# peripherals_1_0.net
KiCad netlist of a schematic drawn in EAGLE
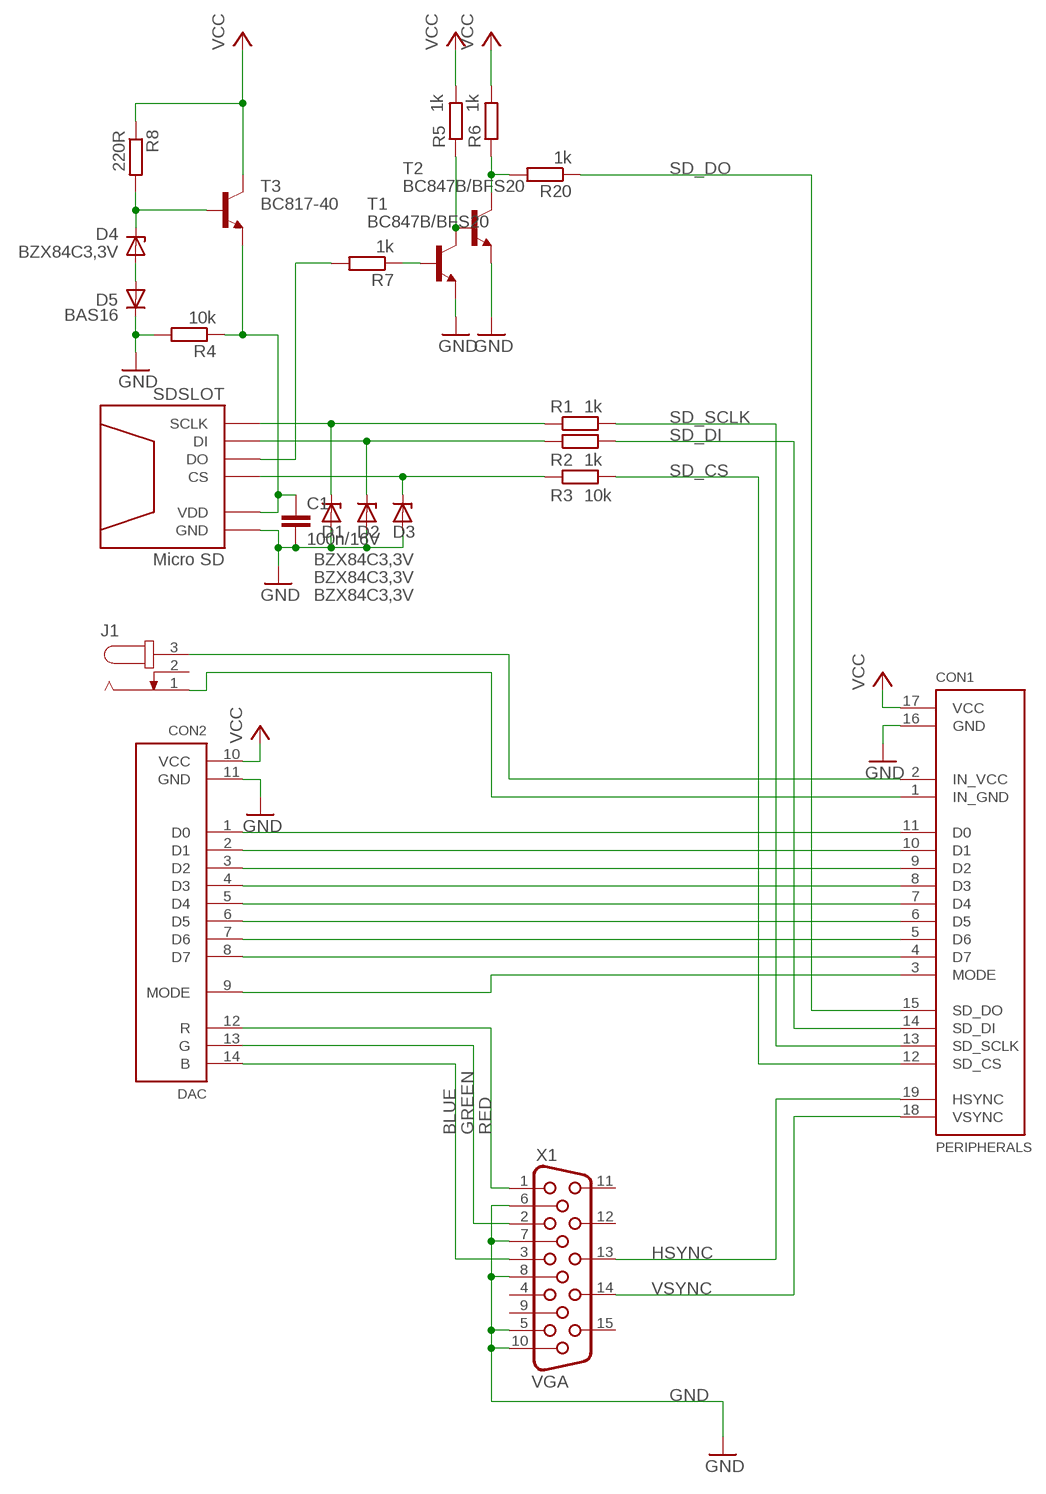
[diagram p0: schematic, sheet 1]

(export (version "E")
  (design (tool "Eeschema 10.0.6"))
  (components
    (comp (ref "C1")
      (value "100n/16V")
      (footprint "eagle-import:C0603")
      (libsource (lib "eagle-import") (part "C-EUC0603"))
    )
    (comp (ref "CON1")
      (value "PERIPHERALS")
      (footprint "eagle-import:PERIPHERALS_CON")
      (libsource (lib "eagle-import") (part "PERIPHERALS"))
    )
    (comp (ref "CON2")
      (value "DAC")
      (footprint "eagle-import:DAC_CON")
      (libsource (lib "eagle-import") (part "DAC"))
    )
    (comp (ref "D1")
      (value "BZX84C3,3V")
      (footprint "eagle-import:SOT23")
      (libsource (lib "eagle-import") (part "ZENER-DIODESOT23"))
    )
    (comp (ref "D2")
      (value "BZX84C3,3V")
      (footprint "eagle-import:SOT23")
      (libsource (lib "eagle-import") (part "ZENER-DIODESOT23"))
    )
    (comp (ref "D3")
      (value "BZX84C3,3V")
      (footprint "eagle-import:SOT23")
      (libsource (lib "eagle-import") (part "ZENER-DIODESOT23"))
    )
    (comp (ref "D4")
      (value "BZX84C3,3V")
      (footprint "eagle-import:SOT23")
      (libsource (lib "eagle-import") (part "ZENER-DIODESOT23"))
    )
    (comp (ref "D5")
      (value "BAS16")
      (footprint "eagle-import:SOT23")
      (libsource (lib "eagle-import") (part "D-A1-C3"))
    )
    (comp (ref "J1")
      (value "JACK-PLUG1")
      (footprint "eagle-import:SPC4078")
      (libsource (lib "eagle-import") (part "JACK-PLUG1"))
    )
    (comp (ref "R1")
      (value "1k")
      (footprint "eagle-import:0204_7")
      (libsource (lib "eagle-import") (part "R-EU_0204/7"))
    )
    (comp (ref "R2")
      (value "1k")
      (footprint "eagle-import:0204_7")
      (libsource (lib "eagle-import") (part "R-EU_0204/7"))
    )
    (comp (ref "R3")
      (value "10k")
      (footprint "eagle-import:0204_7")
      (libsource (lib "eagle-import") (part "R-EU_0204/7"))
    )
    (comp (ref "R4")
      (value "10k")
      (footprint "eagle-import:0204_7")
      (libsource (lib "eagle-import") (part "R-EU_0204/7"))
    )
    (comp (ref "R5")
      (value "1k")
      (footprint "eagle-import:0204_7")
      (libsource (lib "eagle-import") (part "R-EU_0204/7"))
    )
    (comp (ref "R6")
      (value "1k")
      (footprint "eagle-import:0204_7")
      (libsource (lib "eagle-import") (part "R-EU_0204/7"))
    )
    (comp (ref "R7")
      (value "1k")
      (footprint "eagle-import:0204_7")
      (libsource (lib "eagle-import") (part "R-EU_0204/7"))
    )
    (comp (ref "R8")
      (value "220R")
      (footprint "eagle-import:R0603")
      (libsource (lib "eagle-import") (part "R-EU_R0603"))
    )
    (comp (ref "R20")
      (value "1k")
      (footprint "eagle-import:0204_7")
      (libsource (lib "eagle-import") (part "R-EU_0204/7"))
    )
    (comp (ref "SDSLOT")
      (value "Micro SD")
      (footprint "eagle-import:MICRO_SD_ATTEND")
      (libsource (lib "eagle-import") (part "SD_SPI"))
    )
    (comp (ref "T1")
      (value "BC847B/BFS20")
      (footprint "eagle-import:SOT23-BEC")
      (libsource (lib "eagle-import") (part "-NPN-SOT23-BECBC817-40"))
    )
    (comp (ref "T2")
      (value "BC847B/BFS20")
      (footprint "eagle-import:SOT23-BEC")
      (libsource (lib "eagle-import") (part "-NPN-SOT23-BECBC817-40"))
    )
    (comp (ref "T3")
      (value "BC817-40")
      (footprint "eagle-import:SOT23-BEC")
      (libsource (lib "eagle-import") (part "-NPN-SOT23-BECBC817-40"))
    )
    (comp (ref "X1")
      (value "VGA")
      (footprint "eagle-import:HDF15H")
      (libsource (lib "eagle-import") (part "HF15H"))
    )
  )
  (nets
    (net (code "1") (name "/BLUE") (class "Default")
      (node (ref "CON2") (pin "14") (pinfunction "B_14") (pintype "output"))
      (node (ref "X1") (pin "3") (pinfunction "3_3") (pintype "passive"))
    )
    (net (code "2") (name "/GREEN") (class "Default")
      (node (ref "CON2") (pin "13") (pinfunction "G_13") (pintype "output"))
      (node (ref "X1") (pin "2") (pinfunction "2_2") (pintype "passive"))
    )
    (net (code "3") (name "/HSYNC") (class "Default")
      (node (ref "CON1") (pin "19") (pinfunction "HSYNC_19") (pintype "bidirectional"))
      (node (ref "X1") (pin "13") (pinfunction "13_13") (pintype "passive"))
    )
    (net (code "4") (name "/RED") (class "Default")
      (node (ref "CON2") (pin "12") (pinfunction "R_12") (pintype "output"))
      (node (ref "X1") (pin "1") (pinfunction "1_1") (pintype "passive"))
    )
    (net (code "5") (name "/SD_CS") (class "Default")
      (node (ref "CON1") (pin "12") (pinfunction "SD_CS_12") (pintype "bidirectional"))
      (node (ref "R3") (pin "2") (pinfunction "2_2") (pintype "passive"))
    )
    (net (code "6") (name "/SD_DI") (class "Default")
      (node (ref "CON1") (pin "14") (pinfunction "SD_DI_14") (pintype "bidirectional"))
      (node (ref "R2") (pin "2") (pinfunction "2_2") (pintype "passive"))
    )
    (net (code "7") (name "/SD_DO") (class "Default")
      (node (ref "CON1") (pin "15") (pinfunction "SD_DO_15") (pintype "bidirectional"))
      (node (ref "R20") (pin "1") (pinfunction "1_1") (pintype "passive"))
    )
    (net (code "8") (name "/SD_SCLK") (class "Default")
      (node (ref "CON1") (pin "13") (pinfunction "SD_SCLK_13") (pintype "bidirectional"))
      (node (ref "R1") (pin "2") (pinfunction "2_2") (pintype "passive"))
    )
    (net (code "9") (name "/VSYNC") (class "Default")
      (node (ref "CON1") (pin "18") (pinfunction "VSYNC_18") (pintype "bidirectional"))
      (node (ref "X1") (pin "14") (pinfunction "14_14") (pintype "passive"))
    )
    (net (code "10") (name "GND") (class "Default")
      (node (ref "C1") (pin "2") (pinfunction "2_2") (pintype "passive"))
      (node (ref "CON1") (pin "16") (pinfunction "GND_16") (pintype "power_in"))
      (node (ref "CON2") (pin "11") (pinfunction "GND_11") (pintype "power_in"))
      (node (ref "D1") (pin "1") (pinfunction "A_1") (pintype "passive"))
      (node (ref "D2") (pin "1") (pinfunction "A_1") (pintype "passive"))
      (node (ref "D3") (pin "1") (pinfunction "A_1") (pintype "passive"))
      (node (ref "D5") (pin "3") (pinfunction "C_3") (pintype "passive"))
      (node (ref "R4") (pin "2") (pinfunction "2_2") (pintype "passive"))
      (node (ref "SDSLOT") (pin "6") (pinfunction "GND_6") (pintype "power_in"))
      (node (ref "SDSLOT") (pin "CASE1") (pinfunction "GND_CASE1") (pintype "power_in"))
      (node (ref "SDSLOT") (pin "CASE2") (pinfunction "GND_CASE2") (pintype "power_in"))
      (node (ref "SDSLOT") (pin "CASE3") (pinfunction "GND_CASE3") (pintype "power_in"))
      (node (ref "SDSLOT") (pin "CASE4") (pinfunction "GND_CASE4") (pintype "power_in"))
      (node (ref "T1") (pin "E") (pinfunction "E_E") (pintype "passive"))
      (node (ref "T2") (pin "E") (pinfunction "E_E") (pintype "passive"))
      (node (ref "X1") (pin "10") (pinfunction "10_10") (pintype "passive"))
      (node (ref "X1") (pin "5") (pinfunction "5_5") (pintype "passive"))
      (node (ref "X1") (pin "6") (pinfunction "6_6") (pintype "passive"))
      (node (ref "X1") (pin "7") (pinfunction "7_7") (pintype "passive"))
      (node (ref "X1") (pin "8") (pinfunction "8_8") (pintype "passive"))
    )
    (net (code "11") (name "Net-(CON1-D0)") (class "Default")
      (node (ref "CON1") (pin "11") (pinfunction "D0_11") (pintype "bidirectional"))
      (node (ref "CON2") (pin "1") (pinfunction "D0_1") (pintype "input"))
    )
    (net (code "12") (name "Net-(CON1-D1)") (class "Default")
      (node (ref "CON1") (pin "10") (pinfunction "D1_10") (pintype "bidirectional"))
      (node (ref "CON2") (pin "2") (pinfunction "D1_2") (pintype "input"))
    )
    (net (code "13") (name "Net-(CON1-D2)") (class "Default")
      (node (ref "CON1") (pin "9") (pinfunction "D2_9") (pintype "bidirectional"))
      (node (ref "CON2") (pin "3") (pinfunction "D2_3") (pintype "input"))
    )
    (net (code "14") (name "Net-(CON1-D3)") (class "Default")
      (node (ref "CON1") (pin "8") (pinfunction "D3_8") (pintype "bidirectional"))
      (node (ref "CON2") (pin "4") (pinfunction "D3_4") (pintype "input"))
    )
    (net (code "15") (name "Net-(CON1-D4)") (class "Default")
      (node (ref "CON1") (pin "7") (pinfunction "D4_7") (pintype "bidirectional"))
      (node (ref "CON2") (pin "5") (pinfunction "D4_5") (pintype "input"))
    )
    (net (code "16") (name "Net-(CON1-D5)") (class "Default")
      (node (ref "CON1") (pin "6") (pinfunction "D5_6") (pintype "bidirectional"))
      (node (ref "CON2") (pin "6") (pinfunction "D5_6") (pintype "input"))
    )
    (net (code "17") (name "Net-(CON1-D6)") (class "Default")
      (node (ref "CON1") (pin "5") (pinfunction "D6_5") (pintype "bidirectional"))
      (node (ref "CON2") (pin "7") (pinfunction "D6_7") (pintype "input"))
    )
    (net (code "18") (name "Net-(CON1-D7)") (class "Default")
      (node (ref "CON1") (pin "4") (pinfunction "D7_4") (pintype "bidirectional"))
      (node (ref "CON2") (pin "8") (pinfunction "D7_8") (pintype "input"))
    )
    (net (code "19") (name "Net-(CON1-IN_GND)") (class "Default")
      (node (ref "CON1") (pin "1") (pinfunction "IN_GND_1") (pintype "power_in"))
      (node (ref "J1") (pin "1") (pinfunction "1_1") (pintype "passive"))
    )
    (net (code "20") (name "Net-(CON1-IN_VCC)") (class "Default")
      (node (ref "CON1") (pin "2") (pinfunction "IN_VCC_2") (pintype "power_in"))
      (node (ref "J1") (pin "3") (pinfunction "3_3") (pintype "passive"))
    )
    (net (code "21") (name "Net-(CON1-MODE)") (class "Default")
      (node (ref "CON1") (pin "3") (pinfunction "MODE_3") (pintype "bidirectional"))
      (node (ref "CON2") (pin "9") (pinfunction "MODE_9") (pintype "input"))
    )
    (net (code "22") (name "Net-(D1-C)") (class "Default")
      (node (ref "D1") (pin "3") (pinfunction "C_3") (pintype "passive"))
      (node (ref "R1") (pin "1") (pinfunction "1_1") (pintype "passive"))
      (node (ref "SDSLOT") (pin "5") (pinfunction "SCLK_5") (pintype "input"))
    )
    (net (code "23") (name "Net-(D2-C)") (class "Default")
      (node (ref "D2") (pin "3") (pinfunction "C_3") (pintype "passive"))
      (node (ref "R2") (pin "1") (pinfunction "1_1") (pintype "passive"))
      (node (ref "SDSLOT") (pin "3") (pinfunction "DI_3") (pintype "input"))
    )
    (net (code "24") (name "Net-(D3-C)") (class "Default")
      (node (ref "D3") (pin "3") (pinfunction "C_3") (pintype "passive"))
      (node (ref "R3") (pin "1") (pinfunction "1_1") (pintype "passive"))
      (node (ref "SDSLOT") (pin "2") (pinfunction "CS_2") (pintype "input"))
    )
    (net (code "25") (name "Net-(D4-A)") (class "Default")
      (node (ref "D4") (pin "1") (pinfunction "A_1") (pintype "passive"))
      (node (ref "D5") (pin "1") (pinfunction "A_1") (pintype "passive"))
    )
    (net (code "26") (name "Net-(D4-C)") (class "Default")
      (node (ref "D4") (pin "3") (pinfunction "C_3") (pintype "passive"))
      (node (ref "R8") (pin "2") (pinfunction "2_2") (pintype "passive"))
      (node (ref "T3") (pin "B") (pinfunction "B_B") (pintype "passive"))
    )
    (net (code "27") (name "Net-(R5-Pad1)") (class "Default")
      (node (ref "R5") (pin "1") (pinfunction "1_1") (pintype "passive"))
      (node (ref "T1") (pin "C") (pinfunction "C_C") (pintype "passive"))
      (node (ref "T2") (pin "B") (pinfunction "B_B") (pintype "passive"))
    )
    (net (code "28") (name "Net-(R7-Pad1)") (class "Default")
      (node (ref "R7") (pin "1") (pinfunction "1_1") (pintype "passive"))
      (node (ref "T1") (pin "B") (pinfunction "B_B") (pintype "passive"))
    )
    (net (code "29") (name "Net-(R20-Pad2)") (class "Default")
      (node (ref "R20") (pin "2") (pinfunction "2_2") (pintype "passive"))
      (node (ref "R6") (pin "1") (pinfunction "1_1") (pintype "passive"))
      (node (ref "T2") (pin "C") (pinfunction "C_C") (pintype "passive"))
    )
    (net (code "30") (name "Net-(SDSLOT-DO)") (class "Default")
      (node (ref "R7") (pin "2") (pinfunction "2_2") (pintype "passive"))
      (node (ref "SDSLOT") (pin "7") (pinfunction "DO_7") (pintype "output"))
    )
    (net (code "31") (name "Net-(SDSLOT-VDD)") (class "Default")
      (node (ref "C1") (pin "1") (pinfunction "1_1") (pintype "passive"))
      (node (ref "R4") (pin "1") (pinfunction "1_1") (pintype "passive"))
      (node (ref "SDSLOT") (pin "4") (pinfunction "VDD_4") (pintype "power_in"))
      (node (ref "T3") (pin "E") (pinfunction "E_E") (pintype "passive"))
    )
    (net (code "32") (name "VCC") (class "Default")
      (node (ref "CON1") (pin "17") (pinfunction "VCC_17") (pintype "power_in"))
      (node (ref "CON2") (pin "10") (pinfunction "VCC_10") (pintype "power_in"))
      (node (ref "R5") (pin "2") (pinfunction "2_2") (pintype "passive"))
      (node (ref "R6") (pin "2") (pinfunction "2_2") (pintype "passive"))
      (node (ref "R8") (pin "1") (pinfunction "1_1") (pintype "passive"))
      (node (ref "T3") (pin "C") (pinfunction "C_C") (pintype "passive"))
    )
    (net (code "33") (name "unconnected-(J1-Pad2)") (class "Default")
      (node (ref "J1") (pin "2") (pinfunction "2_2") (pintype "passive"))
    )
    (net (code "34") (name "unconnected-(X1-Pad4)") (class "Default")
      (node (ref "X1") (pin "4") (pinfunction "4_4") (pintype "passive"))
    )
    (net (code "35") (name "unconnected-(X1-Pad9)") (class "Default")
      (node (ref "X1") (pin "9") (pinfunction "9_9") (pintype "passive"))
    )
    (net (code "36") (name "unconnected-(X1-Pad11)") (class "Default")
      (node (ref "X1") (pin "11") (pinfunction "11_11") (pintype "passive"))
    )
    (net (code "37") (name "unconnected-(X1-Pad12)") (class "Default")
      (node (ref "X1") (pin "12") (pinfunction "12_12") (pintype "passive"))
    )
    (net (code "38") (name "unconnected-(X1-Pad15)") (class "Default")
      (node (ref "X1") (pin "15") (pinfunction "15_15") (pintype "passive"))
    )
  )
)
